# power-reset_board_v0_2_2.net
KiCad netlist of a schematic drawn in EAGLE
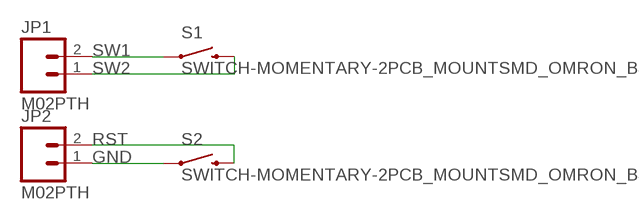
[diagram p0: schematic, sheet 1]

(export (version "E")
  (design (tool "Eeschema 10.0.6"))
  (components
    (comp (ref "JP1")
      (value "M02PTH")
      (footprint "eagle-import:1X02")
      (libsource (lib "eagle-import") (part "M02PTH"))
    )
    (comp (ref "JP2")
      (value "M02PTH")
      (footprint "eagle-import:1X02")
      (libsource (lib "eagle-import") (part "M02PTH"))
    )
    (comp (ref "S1")
      (value "SWITCH-MOMENTARY-2PCB_MOUNTSMD_OMRON_B3S_100X")
      (footprint "eagle-import:TACTILE_SWITCH_LARGE")
      (libsource (lib "eagle-import") (part "SWITCH-MOMENTARY-2SMD_OMRON_B3S_100XPCB_MOUNT"))
    )
    (comp (ref "S2")
      (value "SWITCH-MOMENTARY-2PCB_MOUNTSMD_OMRON_B3S_100X")
      (footprint "eagle-import:TACTILE_SWITCH_LARGE")
      (libsource (lib "eagle-import") (part "SWITCH-MOMENTARY-2SMD_OMRON_B3S_100XPCB_MOUNT"))
    )
  )
  (nets
    (net (code "1") (name "/GND") (class "Default")
      (node (ref "JP2") (pin "1") (pinfunction "1_1") (pintype "passive"))
      (node (ref "S2") (pin "1") (pinfunction "1_1") (pintype "passive"))
      (node (ref "S2") (pin "2") (pinfunction "1_2") (pintype "passive"))
    )
    (net (code "2") (name "/RST") (class "Default")
      (node (ref "JP2") (pin "2") (pinfunction "2_2") (pintype "passive"))
      (node (ref "S2") (pin "3") (pinfunction "2_3") (pintype "passive"))
      (node (ref "S2") (pin "4") (pinfunction "2_4") (pintype "passive"))
    )
    (net (code "3") (name "/SW1") (class "Default")
      (node (ref "JP1") (pin "2") (pinfunction "2_2") (pintype "passive"))
      (node (ref "S1") (pin "1") (pinfunction "1_1") (pintype "passive"))
      (node (ref "S1") (pin "2") (pinfunction "1_2") (pintype "passive"))
    )
    (net (code "4") (name "/SW2") (class "Default")
      (node (ref "JP1") (pin "1") (pinfunction "1_1") (pintype "passive"))
      (node (ref "S1") (pin "3") (pinfunction "2_3") (pintype "passive"))
      (node (ref "S1") (pin "4") (pinfunction "2_4") (pintype "passive"))
    )
  )
)
